# Sheet1.net
KiCad netlist of a schematic drawn in Altium Designer
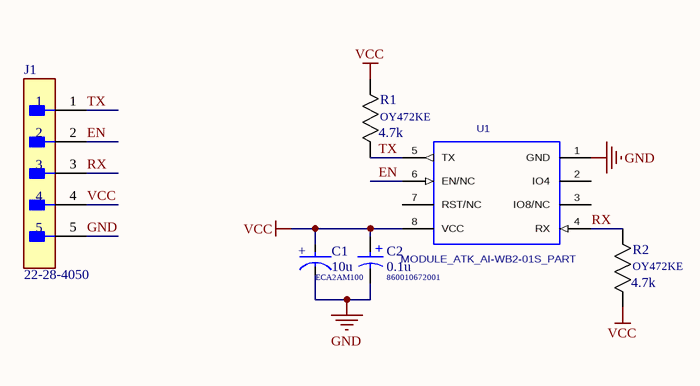
[diagram p0: Sheet1.SchDoc]

(export (version "E")
  (design (tool "Eeschema 10.0.6"))
  (components
    (comp (ref "C1")
      (value "ECA2AM100")
      (footprint "FP-RAD-TH-D_5_0_5-L_11_1-MFG")
      (description "Aluminum Electrolytic Capacitors (Radial Lead Type) 10uF ±20% 100V")
      (fields (field (name "VOLTAGE") "100V") (field (name "TOLERANCE") "20%"))
      (libsource (lib "ECA-2AM100") (part "CMP-05427-000869-1"))
    )
    (comp (ref "C2")
      (value "860010672001")
      (footprint "WCAP-ATG8_D5H11")
      (description "860010672001 Cap Aluminum Lytic 0.1uF 50V 20% (5 X 11mm) Radial 2mm 3.3mA 2000h 85C")
      (fields (field (name "TOLERANCE") "20%"))
      (libsource (lib "860010672001") (part "CMP-03913-54007254-1"))
    )
    (comp (ref "J1")
      (value "22-28-4050")
      (footprint "FP-22-28-4050-MFG")
      (libsource (lib "22-28-4050") (part "CMP-00257-00278173-1"))
    )
    (comp (ref "R1")
      (value "OY472KE")
      (footprint "RES_OY_OHM")
      (description "No Description Available")
      (libsource (lib "OY472KE") (part "OY472KE"))
    )
    (comp (ref "R2")
      (value "OY472KE")
      (footprint "RES_OY_OHM")
      (description "No Description Available")
      (libsource (lib "OY472KE") (part "OY472KE"))
    )
    (comp (ref "U1")
      (value "MODULE_ATK_AI-WB2-01S_PART")
      (footprint "MODULE_ATK_AI-WB2-01S_PCB")
      (libsource (lib "Ai-WB2-01S") (part "MODULE_ATK_AI-WB2-01S_PART"))
    )
  )
  (nets
    (net (code "1") (name "/EN") (class "Default")
      (node (ref "J1") (pin "2") (pinfunction "2_2") (pintype "passive"))
      (node (ref "U1") (pin "6") (pinfunction "EN/NC_6") (pintype "input"))
    )
    (net (code "2") (name "/RX") (class "Default")
      (node (ref "J1") (pin "3") (pinfunction "3_3") (pintype "passive"))
      (node (ref "R2") (pin "1") (pinfunction "1_1") (pintype "passive"))
      (node (ref "U1") (pin "4") (pinfunction "RX_4") (pintype "input"))
    )
    (net (code "3") (name "/TX") (class "Default")
      (node (ref "J1") (pin "1") (pinfunction "1_1") (pintype "passive"))
      (node (ref "R1") (pin "1") (pinfunction "1_1") (pintype "passive"))
      (node (ref "U1") (pin "5") (pinfunction "TX_5") (pintype "output"))
    )
    (net (code "4") (name "GND") (class "Default")
      (node (ref "C1") (pin "1") (pinfunction "C_1") (pintype "passive"))
      (node (ref "C2") (pin "2") (pinfunction "N_2") (pintype "passive"))
      (node (ref "J1") (pin "5") (pinfunction "5_5") (pintype "passive"))
      (node (ref "U1") (pin "1") (pinfunction "GND_1") (pintype "power_in"))
    )
    (net (code "5") (name "VCC") (class "Default")
      (node (ref "C1") (pin "2") (pinfunction "A_2") (pintype "passive"))
      (node (ref "C2") (pin "1") (pinfunction "P_1") (pintype "passive"))
      (node (ref "J1") (pin "4") (pinfunction "4_4") (pintype "passive"))
      (node (ref "R1") (pin "2") (pinfunction "2_2") (pintype "passive"))
      (node (ref "R2") (pin "2") (pinfunction "2_2") (pintype "passive"))
      (node (ref "U1") (pin "8") (pinfunction "VCC_8") (pintype "power_in"))
    )
    (net (code "6") (name "unconnected-(U1-IO4-Pad2)") (class "Default")
      (node (ref "U1") (pin "2") (pinfunction "IO4_2") (pintype "passive"))
    )
    (net (code "7") (name "unconnected-(U1-IO8{slash}NC-Pad3)") (class "Default")
      (node (ref "U1") (pin "3") (pinfunction "IO8/NC_3") (pintype "passive"))
    )
    (net (code "8") (name "unconnected-(U1-RST{slash}NC-Pad7)") (class "Default")
      (node (ref "U1") (pin "7") (pinfunction "RST/NC_7") (pintype "passive"))
    )
  )
)
